# synth.net
KiCad netlist of a schematic drawn in Altium Designer
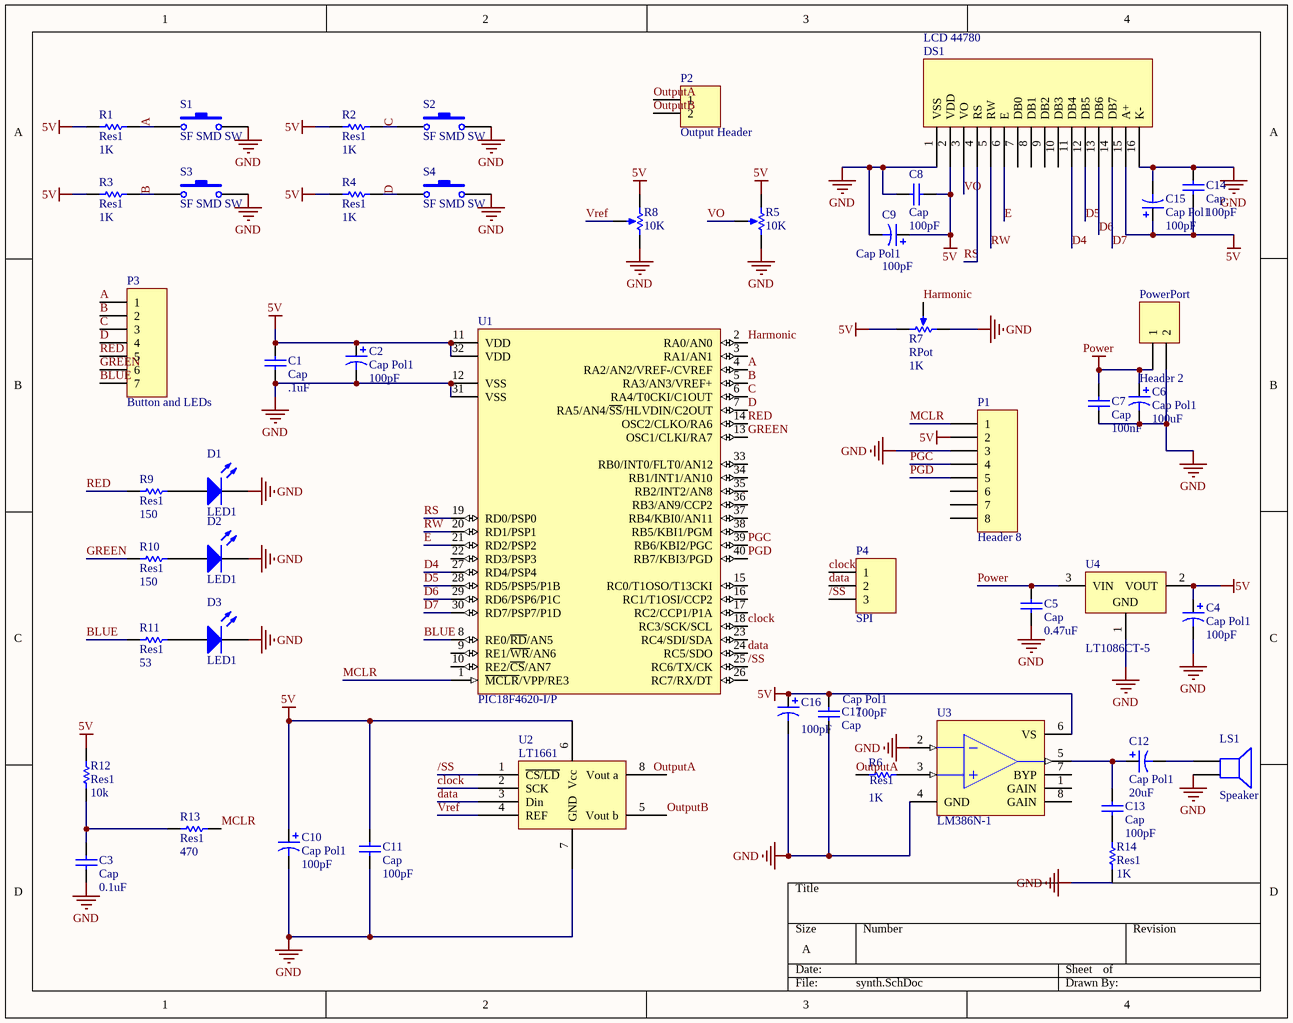
[diagram p0: synth.SchDoc]

(export (version "E")
  (design (tool "Eeschema 10.0.6"))
  (components
    (comp (ref "C1")
      (value "Cap")
      (footprint "RAD-0.3")
      (description "Capacitor")
      (fields (field (name "ALTIUM_VALUE") ".1uF") (field (name "PUBLISHER") "Altium Limited"))
      (libsource (lib "Miscellaneous Devices") (part "Cap"))
    )
    (comp (ref "C2")
      (value "Cap Pol1")
      (footprint "RB7.6-15")
      (description "Polarized Capacitor (Radial)")
      (fields (field (name "ALTIUM_VALUE") "100pF") (field (name "PUBLISHER") "Altium Limited"))
      (libsource (lib "Miscellaneous Devices") (part "Cap Pol1"))
    )
    (comp (ref "C3")
      (value "Cap")
      (footprint "RAD-0.3")
      (description "Capacitor")
      (fields (field (name "ALTIUM_VALUE") "0.1uF") (field (name "PUBLISHER") "Altium Limited"))
      (libsource (lib "Miscellaneous Devices") (part "Cap"))
    )
    (comp (ref "C4")
      (value "Cap Pol1")
      (footprint "RB7.6-15")
      (description "Polarized Capacitor (Radial)")
      (fields (field (name "ALTIUM_VALUE") "100pF") (field (name "PUBLISHER") "Altium Limited"))
      (libsource (lib "Miscellaneous Devices") (part "Cap Pol1"))
    )
    (comp (ref "C5")
      (value "Cap")
      (footprint "RAD-0.3")
      (description "Capacitor")
      (fields (field (name "ALTIUM_VALUE") "0.47uF") (field (name "PUBLISHER") "Altium Limited"))
      (libsource (lib "Miscellaneous Devices") (part "Cap"))
    )
    (comp (ref "C6")
      (value "Cap Pol1")
      (footprint "RB7.6-15")
      (description "Polarized Capacitor (Radial)")
      (fields (field (name "ALTIUM_VALUE") "100uF") (field (name "PUBLISHER") "Altium Limited"))
      (libsource (lib "Miscellaneous Devices") (part "Cap Pol1"))
    )
    (comp (ref "C7")
      (value "Cap")
      (footprint "RAD-0.3")
      (description "Capacitor")
      (fields (field (name "ALTIUM_VALUE") "100nF") (field (name "PUBLISHER") "Altium Limited"))
      (libsource (lib "Miscellaneous Devices") (part "Cap"))
    )
    (comp (ref "C8")
      (value "Cap")
      (footprint "RAD-0.3")
      (description "Capacitor")
      (fields (field (name "ALTIUM_VALUE") "100pF") (field (name "PUBLISHER") "Altium Limited"))
      (libsource (lib "Miscellaneous Devices") (part "Cap"))
    )
    (comp (ref "C9")
      (value "Cap Pol1")
      (footprint "RB7.6-15")
      (description "Polarized Capacitor (Radial)")
      (fields (field (name "ALTIUM_VALUE") "100pF") (field (name "PUBLISHER") "Altium Limited"))
      (libsource (lib "Miscellaneous Devices") (part "Cap Pol1"))
    )
    (comp (ref "C10")
      (value "Cap Pol1")
      (footprint "RB7.6-15")
      (description "Polarized Capacitor (Radial)")
      (fields (field (name "ALTIUM_VALUE") "100pF") (field (name "PUBLISHER") "Altium Limited"))
      (libsource (lib "Miscellaneous Devices") (part "Cap Pol1"))
    )
    (comp (ref "C11")
      (value "Cap")
      (footprint "RAD-0.3")
      (description "Capacitor")
      (fields (field (name "ALTIUM_VALUE") "100pF") (field (name "PUBLISHER") "Altium Limited"))
      (libsource (lib "Miscellaneous Devices") (part "Cap"))
    )
    (comp (ref "C12")
      (value "Cap Pol1")
      (footprint "RB7.6-15")
      (description "Polarized Capacitor (Radial)")
      (fields (field (name "ALTIUM_VALUE") "20uF") (field (name "PUBLISHER") "Altium Limited"))
      (libsource (lib "Miscellaneous Devices") (part "Cap Pol1"))
    )
    (comp (ref "C13")
      (value "Cap")
      (footprint "RAD-0.3")
      (description "Capacitor")
      (fields (field (name "ALTIUM_VALUE") "100pF") (field (name "PUBLISHER") "Altium Limited"))
      (libsource (lib "Miscellaneous Devices") (part "Cap"))
    )
    (comp (ref "C14")
      (value "Cap")
      (footprint "RAD-0.3")
      (description "Capacitor")
      (fields (field (name "ALTIUM_VALUE") "100pF") (field (name "PUBLISHER") "Altium Limited"))
      (libsource (lib "Miscellaneous Devices") (part "Cap"))
    )
    (comp (ref "C15")
      (value "Cap Pol1")
      (footprint "RB7.6-15")
      (description "Polarized Capacitor (Radial)")
      (fields (field (name "ALTIUM_VALUE") "100pF") (field (name "PUBLISHER") "Altium Limited"))
      (libsource (lib "Miscellaneous Devices") (part "Cap Pol1"))
    )
    (comp (ref "C16")
      (value "Cap Pol1")
      (footprint "RB7.6-15")
      (description "Polarized Capacitor (Radial)")
      (fields (field (name "ALTIUM_VALUE") "100pF") (field (name "PUBLISHER") "Altium Limited"))
      (libsource (lib "Miscellaneous Devices") (part "Cap Pol1"))
    )
    (comp (ref "C17")
      (value "Cap")
      (footprint "RAD-0.3")
      (description "Capacitor")
      (fields (field (name "ALTIUM_VALUE") "100pF") (field (name "PUBLISHER") "Altium Limited"))
      (libsource (lib "Miscellaneous Devices") (part "Cap"))
    )
    (comp (ref "D1")
      (value "LED1")
      (footprint "LED-1")
      (description "Typical RED GaAs LED")
      (fields (field (name "PUBLISHER") "Altium Limited"))
      (libsource (lib "Miscellaneous Devices") (part "LED1"))
    )
    (comp (ref "D2")
      (value "LED1")
      (footprint "LED-1")
      (description "Typical RED GaAs LED")
      (fields (field (name "PUBLISHER") "Altium Limited"))
      (libsource (lib "Miscellaneous Devices") (part "LED1"))
    )
    (comp (ref "D3")
      (value "LED1")
      (footprint "LED-1")
      (description "Typical RED GaAs LED")
      (fields (field (name "PUBLISHER") "Altium Limited"))
      (libsource (lib "Miscellaneous Devices") (part "LED1"))
    )
    (comp (ref "DS1")
      (value "LCD 44780")
      (footprint "OLED 16x2")
      (libsource (lib "ECE LIB 21") (part "LCD 44780"))
    )
    (comp (ref "LS1")
      (value "Speaker")
      (footprint "PIN2")
      (description "Loudspeaker")
      (fields (field (name "PUBLISHER") "Altium Limited"))
      (libsource (lib "Miscellaneous Devices") (part "Speaker"))
    )
    (comp (ref "P1")
      (value "Header 8")
      (footprint "HDR1X8")
      (description "Header, 8-Pin")
      (fields (field (name "PUBLISHER") "Altium Limited"))
      (libsource (lib "Miscellaneous Connectors") (part "Header 8"))
    )
    (comp (ref "P2")
      (value "Output Header")
      (footprint "HDR1X2")
      (description "Header, 2-Pin")
      (fields (field (name "PUBLISHER") "Altium Limited"))
      (libsource (lib "Miscellaneous Connectors") (part "Header 2"))
    )
    (comp (ref "P3")
      (value "Button and LEDs")
      (footprint "HDR1X7")
      (description "Header, 7-Pin")
      (fields (field (name "PUBLISHER") "Altium Limited"))
      (libsource (lib "Miscellaneous Connectors") (part "Header 7"))
    )
    (comp (ref "P4")
      (value "SPI")
      (footprint "HDR1X3")
      (description "Header, 3-Pin")
      (fields (field (name "PUBLISHER") "Altium Limited"))
      (libsource (lib "Miscellaneous Connectors") (part "Header 3"))
    )
    (comp (ref "PowerPort")
      (value "Header 2")
      (footprint "HDR1X2")
      (description "Header, 2-Pin")
      (fields (field (name "PUBLISHER") "Altium Limited"))
      (libsource (lib "") (part "Header 2_1"))
    )
    (comp (ref "R1")
      (value "Res1")
      (footprint "AXIAL-0.3")
      (description "Resistor")
      (fields (field (name "ALTIUM_VALUE") "1K") (field (name "PUBLISHER") "Altium Limited"))
      (libsource (lib "Miscellaneous Devices") (part "Res1"))
    )
    (comp (ref "R2")
      (value "Res1")
      (footprint "AXIAL-0.3")
      (description "Resistor")
      (fields (field (name "ALTIUM_VALUE") "1K") (field (name "PUBLISHER") "Altium Limited"))
      (libsource (lib "Miscellaneous Devices") (part "Res1"))
    )
    (comp (ref "R3")
      (value "Res1")
      (footprint "AXIAL-0.3")
      (description "Resistor")
      (fields (field (name "ALTIUM_VALUE") "1K") (field (name "PUBLISHER") "Altium Limited"))
      (libsource (lib "Miscellaneous Devices") (part "Res1"))
    )
    (comp (ref "R4")
      (value "Res1")
      (footprint "AXIAL-0.3")
      (description "Resistor")
      (fields (field (name "ALTIUM_VALUE") "1K") (field (name "PUBLISHER") "Altium Limited"))
      (libsource (lib "Miscellaneous Devices") (part "Res1"))
    )
    (comp (ref "R5")
      (value "10K")
      (footprint "Rpot Square in line")
      (description "Potentiometer")
      (fields (field (name "Comment") "RPot_3") (field (name "PUBLISHER") "Altium Limited"))
      (libsource (lib "ECE LIB 21") (part "RPot_7"))
    )
    (comp (ref "R6")
      (value "Res1")
      (footprint "AXIAL-0.3")
      (description "Resistor")
      (fields (field (name "ALTIUM_VALUE") "1K") (field (name "PUBLISHER") "Altium Limited"))
      (libsource (lib "Miscellaneous Devices") (part "Res1"))
    )
    (comp (ref "R7")
      (value "RPot")
      (footprint "VR5")
      (description "Potentiometer")
      (fields (field (name "ALTIUM_VALUE") "1K") (field (name "PUBLISHER") "Altium Limited"))
      (libsource (lib "Miscellaneous Devices") (part "RPot"))
    )
    (comp (ref "R8")
      (value "10K")
      (footprint "Rpot Square in line")
      (description "Potentiometer")
      (fields (field (name "Comment") "RPot_3") (field (name "PUBLISHER") "Altium Limited"))
      (libsource (lib "ECE LIB 21") (part "RPot_7"))
    )
    (comp (ref "R9")
      (value "Res1")
      (footprint "AXIAL-0.3")
      (description "Resistor")
      (fields (field (name "ALTIUM_VALUE") "150") (field (name "PUBLISHER") "Altium Limited"))
      (libsource (lib "Miscellaneous Devices") (part "Res1"))
    )
    (comp (ref "R10")
      (value "Res1")
      (footprint "AXIAL-0.3")
      (description "Resistor")
      (fields (field (name "ALTIUM_VALUE") "150") (field (name "PUBLISHER") "Altium Limited"))
      (libsource (lib "Miscellaneous Devices") (part "Res1"))
    )
    (comp (ref "R11")
      (value "Res1")
      (footprint "AXIAL-0.3")
      (description "Resistor")
      (fields (field (name "ALTIUM_VALUE") "53") (field (name "PUBLISHER") "Altium Limited"))
      (libsource (lib "Miscellaneous Devices") (part "Res1"))
    )
    (comp (ref "R12")
      (value "Res1")
      (footprint "AXIAL-0.3")
      (description "Resistor")
      (fields (field (name "ALTIUM_VALUE") "10k") (field (name "PUBLISHER") "Altium Limited"))
      (libsource (lib "Miscellaneous Devices") (part "Res1"))
    )
    (comp (ref "R13")
      (value "Res1")
      (footprint "AXIAL-0.3")
      (description "Resistor")
      (fields (field (name "ALTIUM_VALUE") "470") (field (name "PUBLISHER") "Altium Limited"))
      (libsource (lib "Miscellaneous Devices") (part "Res1"))
    )
    (comp (ref "R14")
      (value "Res1")
      (footprint "AXIAL-0.3")
      (description "Resistor")
      (fields (field (name "ALTIUM_VALUE") "1K") (field (name "PUBLISHER") "Altium Limited"))
      (libsource (lib "Miscellaneous Devices") (part "Res1"))
    )
    (comp (ref "S1")
      (value "SF SMD SW")
      (footprint "SW PB")
      (description "DIGIKEY SW400-ND")
      (fields (field (name "PUBLISHER") "Altium Limited"))
      (libsource (lib "ECE LIB 21") (part "SW-PB_1"))
    )
    (comp (ref "S2")
      (value "SF SMD SW")
      (footprint "SW PB")
      (description "DIGIKEY SW400-ND")
      (fields (field (name "PUBLISHER") "Altium Limited"))
      (libsource (lib "ECE LIB 21") (part "SW-PB_1"))
    )
    (comp (ref "S3")
      (value "SF SMD SW")
      (footprint "SW PB")
      (description "DIGIKEY SW400-ND")
      (fields (field (name "PUBLISHER") "Altium Limited"))
      (libsource (lib "ECE LIB 21") (part "SW-PB_1"))
    )
    (comp (ref "S4")
      (value "SF SMD SW")
      (footprint "SW PB")
      (description "DIGIKEY SW400-ND")
      (fields (field (name "PUBLISHER") "Altium Limited"))
      (libsource (lib "ECE LIB 21") (part "SW-PB_1"))
    )
    (comp (ref "U1")
      (value "PIC18F4620-I/P")
      (footprint "PDIP600-P40")
      (libsource (lib "ECE LIB 21") (part "PIC18F4620-I/P"))
    )
    (comp (ref "U2") (value "LT1661") (footprint "DIP-8") (libsource (lib "ECE LIB 21") (part "LT1661")))
    (comp (ref "U3")
      (value "LM386N-1")
      (footprint "DIP-8")
      (description "Low-Voltage Audio Power Amplifier")
      (fields (field (name "PUBLISHER") "Altium Limited"))
      (libsource (lib "ECE LIB 21") (part "LM386N-1"))
    )
    (comp (ref "U4")
      (value "LT1086CT-5")
      (footprint "LT-T-3")
      (description "1.5 A Low Dropout Positive Regulator, 2.55 to 25 V Vin, 5 V Vout, 3-pin FM (T-3), 0 to 150 degC")
      (fields (field (name "MANUFACTURER") "Linear Technology"))
      (libsource (lib "ECE LIB 21") (part "LT1086CT-5"))
    )
  )
  (nets
    (net (code "1") (name "/A") (class "Default")
      (node (ref "P3") (pin "1") (pinfunction "1_1") (pintype "passive"))
      (node (ref "R1") (pin "2") (pinfunction "2_2") (pintype "passive"))
      (node (ref "S1") (pin "1") (pinfunction "1_1") (pintype "passive"))
      (node (ref "U1") (pin "4") (pinfunction "RA2/AN2/VREF-/CVREF_4") (pintype "bidirectional"))
    )
    (net (code "2") (name "/B") (class "Default")
      (node (ref "P3") (pin "2") (pinfunction "2_2") (pintype "passive"))
      (node (ref "R3") (pin "2") (pinfunction "2_2") (pintype "passive"))
      (node (ref "S3") (pin "1") (pinfunction "1_1") (pintype "passive"))
      (node (ref "U1") (pin "5") (pinfunction "RA3/AN3/VREF+_5") (pintype "bidirectional"))
    )
    (net (code "3") (name "/BLUE") (class "Default")
      (node (ref "P3") (pin "7") (pinfunction "7_7") (pintype "passive"))
      (node (ref "R11") (pin "1") (pinfunction "1_1") (pintype "passive"))
      (node (ref "U1") (pin "8") (pinfunction "RE0/~{RD}/AN5_8") (pintype "bidirectional"))
    )
    (net (code "4") (name "/C") (class "Default")
      (node (ref "P3") (pin "3") (pinfunction "3_3") (pintype "passive"))
      (node (ref "R2") (pin "2") (pinfunction "2_2") (pintype "passive"))
      (node (ref "S2") (pin "1") (pinfunction "1_1") (pintype "passive"))
      (node (ref "U1") (pin "6") (pinfunction "RA4/T0CKI/C1OUT_6") (pintype "bidirectional"))
    )
    (net (code "5") (name "/D") (class "Default")
      (node (ref "P3") (pin "4") (pinfunction "4_4") (pintype "passive"))
      (node (ref "R4") (pin "2") (pinfunction "2_2") (pintype "passive"))
      (node (ref "S4") (pin "1") (pinfunction "1_1") (pintype "passive"))
      (node (ref "U1") (pin "7") (pinfunction "RA5/AN4/~{SS}/HLVDIN/C2OUT_7") (pintype "bidirectional"))
    )
    (net (code "6") (name "/D4") (class "Default")
      (node (ref "DS1") (pin "11") (pinfunction "DB4_11") (pintype "passive"))
      (node (ref "U1") (pin "27") (pinfunction "RD4/PSP4_27") (pintype "bidirectional"))
    )
    (net (code "7") (name "/D5") (class "Default")
      (node (ref "DS1") (pin "12") (pinfunction "DB5_12") (pintype "passive"))
      (node (ref "U1") (pin "28") (pinfunction "RD5/PSP5/P1B_28") (pintype "bidirectional"))
    )
    (net (code "8") (name "/D6") (class "Default")
      (node (ref "DS1") (pin "13") (pinfunction "DB6_13") (pintype "passive"))
      (node (ref "U1") (pin "29") (pinfunction "RD6/PSP6/P1C_29") (pintype "bidirectional"))
    )
    (net (code "9") (name "/D7") (class "Default")
      (node (ref "DS1") (pin "14") (pinfunction "DB7_14") (pintype "passive"))
      (node (ref "U1") (pin "30") (pinfunction "RD7/PSP7/P1D_30") (pintype "bidirectional"))
    )
    (net (code "10") (name "/E") (class "Default")
      (node (ref "DS1") (pin "6") (pinfunction "E_6") (pintype "passive"))
      (node (ref "U1") (pin "21") (pinfunction "RD2/PSP2_21") (pintype "bidirectional"))
    )
    (net (code "11") (name "/GREEN") (class "Default")
      (node (ref "P3") (pin "6") (pinfunction "6_6") (pintype "passive"))
      (node (ref "R10") (pin "1") (pinfunction "1_1") (pintype "passive"))
      (node (ref "U1") (pin "13") (pinfunction "OSC1/CLKI/RA7_13") (pintype "bidirectional"))
    )
    (net (code "12") (name "/Harmonic") (class "Default")
      (node (ref "R7") (pin "3") (pinfunction "TAP_3") (pintype "passive"))
      (node (ref "U1") (pin "2") (pinfunction "RA0/AN0_2") (pintype "bidirectional"))
    )
    (net (code "13") (name "/MCLR") (class "Default")
      (node (ref "P1") (pin "1") (pinfunction "1_1") (pintype "passive"))
      (node (ref "R13") (pin "2") (pinfunction "2_2") (pintype "passive"))
      (node (ref "U1") (pin "1") (pinfunction "~{MCLR}/VPP/RE3_1") (pintype "input"))
    )
    (net (code "14") (name "/OutputA") (class "Default")
      (node (ref "P2") (pin "1") (pinfunction "1_1") (pintype "passive"))
      (node (ref "R6") (pin "1") (pinfunction "1_1") (pintype "passive"))
    )
    (net (code "15") (name "/OutputB") (class "Default")
      (node (ref "P2") (pin "2") (pinfunction "2_2") (pintype "passive"))
      (node (ref "U2") (pin "5") (pinfunction "Vout_b_5") (pintype "passive"))
    )
    (net (code "16") (name "/PGC") (class "Default")
      (node (ref "P1") (pin "4") (pinfunction "4_4") (pintype "passive"))
      (node (ref "U1") (pin "39") (pinfunction "RB6/KBI2/PGC_39") (pintype "bidirectional"))
    )
    (net (code "17") (name "/PGD") (class "Default")
      (node (ref "P1") (pin "5") (pinfunction "5_5") (pintype "passive"))
      (node (ref "U1") (pin "40") (pinfunction "RB7/KBI3/PGD_40") (pintype "bidirectional"))
    )
    (net (code "18") (name "/RED") (class "Default")
      (node (ref "P3") (pin "5") (pinfunction "5_5") (pintype "passive"))
      (node (ref "R9") (pin "1") (pinfunction "1_1") (pintype "passive"))
      (node (ref "U1") (pin "14") (pinfunction "OSC2/CLKO/RA6_14") (pintype "bidirectional"))
    )
    (net (code "19") (name "/RS") (class "Default")
      (node (ref "DS1") (pin "4") (pinfunction "RS_4") (pintype "passive"))
      (node (ref "U1") (pin "19") (pinfunction "RD0/PSP0_19") (pintype "bidirectional"))
    )
    (net (code "20") (name "/RW") (class "Default")
      (node (ref "DS1") (pin "5") (pinfunction "RW_5") (pintype "passive"))
      (node (ref "U1") (pin "20") (pinfunction "RD1/PSP1_20") (pintype "bidirectional"))
    )
    (net (code "21") (name "/VO") (class "Default")
      (node (ref "DS1") (pin "3") (pinfunction "VO_3") (pintype "passive"))
      (node (ref "R5") (pin "2") (pinfunction "TAP_2") (pintype "passive"))
    )
    (net (code "22") (name "/Vref") (class "Default")
      (node (ref "R8") (pin "2") (pinfunction "TAP_2") (pintype "passive"))
      (node (ref "U2") (pin "4") (pinfunction "REF_4") (pintype "passive"))
    )
    (net (code "23") (name "/clock") (class "Default")
      (node (ref "P4") (pin "1") (pinfunction "1_1") (pintype "passive"))
      (node (ref "U1") (pin "18") (pinfunction "RC3/SCK/SCL_18") (pintype "bidirectional"))
      (node (ref "U2") (pin "2") (pinfunction "SCK_2") (pintype "passive"))
    )
    (net (code "24") (name "/data") (class "Default")
      (node (ref "P4") (pin "2") (pinfunction "2_2") (pintype "passive"))
      (node (ref "U1") (pin "24") (pinfunction "RC5/SDO_24") (pintype "bidirectional"))
      (node (ref "U2") (pin "3") (pinfunction "Din_3") (pintype "passive"))
    )
    (net (code "25") (name "/{slash}SS") (class "Default")
      (node (ref "P4") (pin "3") (pinfunction "3_3") (pintype "passive"))
      (node (ref "U1") (pin "25") (pinfunction "RC6/TX/CK_25") (pintype "bidirectional"))
      (node (ref "U2") (pin "1") (pinfunction "~{CS/LD}_1") (pintype "passive"))
    )
    (net (code "26") (name "5V") (class "Default")
      (node (ref "C1") (pin "2") (pinfunction "2_2") (pintype "passive"))
      (node (ref "C10") (pin "1") (pinfunction "1_1") (pintype "passive"))
      (node (ref "C11") (pin "2") (pinfunction "2_2") (pintype "passive"))
      (node (ref "C14") (pin "1") (pinfunction "1_1") (pintype "passive"))
      (node (ref "C15") (pin "1") (pinfunction "1_1") (pintype "passive"))
      (node (ref "C16") (pin "1") (pinfunction "1_1") (pintype "passive"))
      (node (ref "C17") (pin "2") (pinfunction "2_2") (pintype "passive"))
      (node (ref "C2") (pin "1") (pinfunction "1_1") (pintype "passive"))
      (node (ref "C4") (pin "1") (pinfunction "1_1") (pintype "passive"))
      (node (ref "C8") (pin "2") (pinfunction "2_2") (pintype "passive"))
      (node (ref "C9") (pin "1") (pinfunction "1_1") (pintype "passive"))
      (node (ref "DS1") (pin "15") (pinfunction "A+_15") (pintype "passive"))
      (node (ref "DS1") (pin "2") (pinfunction "VDD_2") (pintype "passive"))
      (node (ref "P1") (pin "2") (pinfunction "2_2") (pintype "passive"))
      (node (ref "R1") (pin "1") (pinfunction "1_1") (pintype "passive"))
      (node (ref "R12") (pin "2") (pinfunction "2_2") (pintype "passive"))
      (node (ref "R2") (pin "1") (pinfunction "1_1") (pintype "passive"))
      (node (ref "R3") (pin "1") (pinfunction "1_1") (pintype "passive"))
      (node (ref "R4") (pin "1") (pinfunction "1_1") (pintype "passive"))
      (node (ref "R5") (pin "1") (pinfunction "TOP_1") (pintype "passive"))
      (node (ref "R7") (pin "2") (pinfunction "BOT_2") (pintype "passive"))
      (node (ref "R8") (pin "1") (pinfunction "TOP_1") (pintype "passive"))
      (node (ref "U1") (pin "11") (pinfunction "VDD_11") (pintype "power_in"))
      (node (ref "U1") (pin "32") (pinfunction "VDD_32") (pintype "power_in"))
      (node (ref "U2") (pin "6") (pinfunction "Vcc_6") (pintype "passive"))
      (node (ref "U3") (pin "6") (pinfunction "VS_6") (pintype "power_in"))
      (node (ref "U4") (pin "2") (pinfunction "VOUT_2") (pintype "power_in"))
    )
    (net (code "27") (name "GND") (class "Default")
      (node (ref "C1") (pin "1") (pinfunction "1_1") (pintype "passive"))
      (node (ref "C10") (pin "2") (pinfunction "2_2") (pintype "passive"))
      (node (ref "C11") (pin "1") (pinfunction "1_1") (pintype "passive"))
      (node (ref "C14") (pin "2") (pinfunction "2_2") (pintype "passive"))
      (node (ref "C15") (pin "2") (pinfunction "2_2") (pintype "passive"))
      (node (ref "C16") (pin "2") (pinfunction "2_2") (pintype "passive"))
      (node (ref "C17") (pin "1") (pinfunction "1_1") (pintype "passive"))
      (node (ref "C2") (pin "2") (pinfunction "2_2") (pintype "passive"))
      (node (ref "C3") (pin "1") (pinfunction "1_1") (pintype "passive"))
      (node (ref "C4") (pin "2") (pinfunction "2_2") (pintype "passive"))
      (node (ref "C5") (pin "1") (pinfunction "1_1") (pintype "passive"))
      (node (ref "C6") (pin "2") (pinfunction "2_2") (pintype "passive"))
      (node (ref "C7") (pin "1") (pinfunction "1_1") (pintype "passive"))
      (node (ref "C8") (pin "1") (pinfunction "1_1") (pintype "passive"))
      (node (ref "C9") (pin "2") (pinfunction "2_2") (pintype "passive"))
      (node (ref "D1") (pin "2") (pinfunction "K_2") (pintype "passive"))
      (node (ref "D2") (pin "2") (pinfunction "K_2") (pintype "passive"))
      (node (ref "D3") (pin "2") (pinfunction "K_2") (pintype "passive"))
      (node (ref "DS1") (pin "1") (pinfunction "VSS_1") (pintype "passive"))
      (node (ref "DS1") (pin "16") (pinfunction "K-_16") (pintype "passive"))
      (node (ref "LS1") (pin "2") (pinfunction "2_2") (pintype "passive"))
      (node (ref "P1") (pin "3") (pinfunction "3_3") (pintype "passive"))
      (node (ref "PowerPort") (pin "2") (pinfunction "2_2") (pintype "passive"))
      (node (ref "R14") (pin "1") (pinfunction "1_1") (pintype "passive"))
      (node (ref "R5") (pin "3") (pinfunction "BOT_3") (pintype "passive"))
      (node (ref "R7") (pin "1") (pinfunction "TOP_1") (pintype "passive"))
      (node (ref "R8") (pin "3") (pinfunction "BOT_3") (pintype "passive"))
      (node (ref "S1") (pin "2") (pinfunction "2_2") (pintype "passive"))
      (node (ref "S2") (pin "2") (pinfunction "2_2") (pintype "passive"))
      (node (ref "S3") (pin "2") (pinfunction "2_2") (pintype "passive"))
      (node (ref "S4") (pin "2") (pinfunction "2_2") (pintype "passive"))
      (node (ref "U1") (pin "12") (pinfunction "VSS_12") (pintype "power_in"))
      (node (ref "U1") (pin "31") (pinfunction "VSS_31") (pintype "power_in"))
      (node (ref "U2") (pin "7") (pinfunction "GND_7") (pintype "passive"))
      (node (ref "U3") (pin "2") (pinfunction "IN-_2") (pintype "input"))
      (node (ref "U3") (pin "4") (pinfunction "GND_4") (pintype "power_in"))
      (node (ref "U4") (pin "1") (pinfunction "GND_1") (pintype "power_in"))
    )
    (net (code "28") (name "Net-(C3-Pad2)") (class "Default")
      (node (ref "C3") (pin "2") (pinfunction "2_2") (pintype "passive"))
      (node (ref "R12") (pin "1") (pinfunction "1_1") (pintype "passive"))
      (node (ref "R13") (pin "1") (pinfunction "1_1") (pintype "passive"))
    )
    (net (code "29") (name "Net-(C12-Pad2)") (class "Default")
      (node (ref "C12") (pin "2") (pinfunction "2_2") (pintype "passive"))
      (node (ref "LS1") (pin "1") (pinfunction "1_1") (pintype "passive"))
    )
    (net (code "30") (name "Net-(C13-Pad1)") (class "Default")
      (node (ref "C13") (pin "1") (pinfunction "1_1") (pintype "passive"))
      (node (ref "R14") (pin "2") (pinfunction "2_2") (pintype "passive"))
    )
    (net (code "31") (name "Net-(D1-A)") (class "Default")
      (node (ref "D1") (pin "1") (pinfunction "A_1") (pintype "passive"))
      (node (ref "R9") (pin "2") (pinfunction "2_2") (pintype "passive"))
    )
    (net (code "32") (name "Net-(D2-A)") (class "Default")
      (node (ref "D2") (pin "1") (pinfunction "A_1") (pintype "passive"))
      (node (ref "R10") (pin "2") (pinfunction "2_2") (pintype "passive"))
    )
    (net (code "33") (name "Net-(D3-A)") (class "Default")
      (node (ref "D3") (pin "1") (pinfunction "A_1") (pintype "passive"))
      (node (ref "R11") (pin "2") (pinfunction "2_2") (pintype "passive"))
    )
    (net (code "34") (name "Net-(U3-IN+)") (class "Default")
      (node (ref "R6") (pin "2") (pinfunction "2_2") (pintype "passive"))
      (node (ref "U3") (pin "3") (pinfunction "IN+_3") (pintype "input"))
    )
    (net (code "35") (name "Net-(U3-OUT)") (class "Default")
      (node (ref "C12") (pin "1") (pinfunction "1_1") (pintype "passive"))
      (node (ref "C13") (pin "2") (pinfunction "2_2") (pintype "passive"))
      (node (ref "U3") (pin "5") (pinfunction "OUT_5") (pintype "output"))
    )
    (net (code "36") (name "Power") (class "Default")
      (node (ref "C5") (pin "2") (pinfunction "2_2") (pintype "passive"))
      (node (ref "C6") (pin "1") (pinfunction "1_1") (pintype "passive"))
      (node (ref "C7") (pin "2") (pinfunction "2_2") (pintype "passive"))
      (node (ref "PowerPort") (pin "1") (pinfunction "1_1") (pintype "passive"))
      (node (ref "U4") (pin "3") (pinfunction "VIN_3") (pintype "power_in"))
    )
    (net (code "37") (name "unconnected-(DS1-DB0-Pad7)") (class "Default")
      (node (ref "DS1") (pin "7") (pinfunction "DB0_7") (pintype "passive"))
    )
    (net (code "38") (name "unconnected-(DS1-DB1-Pad8)") (class "Default")
      (node (ref "DS1") (pin "8") (pinfunction "DB1_8") (pintype "passive"))
    )
    (net (code "39") (name "unconnected-(DS1-DB2-Pad9)") (class "Default")
      (node (ref "DS1") (pin "9") (pinfunction "DB2_9") (pintype "passive"))
    )
    (net (code "40") (name "unconnected-(DS1-DB3-Pad10)") (class "Default")
      (node (ref "DS1") (pin "10") (pinfunction "DB3_10") (pintype "passive"))
    )
    (net (code "41") (name "unconnected-(P1-Pad6)") (class "Default")
      (node (ref "P1") (pin "6") (pinfunction "6_6") (pintype "passive"))
    )
    (net (code "42") (name "unconnected-(P1-Pad7)") (class "Default")
      (node (ref "P1") (pin "7") (pinfunction "7_7") (pintype "passive"))
    )
    (net (code "43") (name "unconnected-(P1-Pad8)") (class "Default")
      (node (ref "P1") (pin "8") (pinfunction "8_8") (pintype "passive"))
    )
    (net (code "44") (name "unconnected-(U1-RA1{slash}AN1-Pad3)") (class "Default")
      (node (ref "U1") (pin "3") (pinfunction "RA1/AN1_3") (pintype "bidirectional"))
    )
    (net (code "45") (name "unconnected-(U1-RB0{slash}INT0{slash}FLT0{slash}AN12-Pad33)") (class "Default")
      (node (ref "U1") (pin "33") (pinfunction "RB0/INT0/FLT0/AN12_33") (pintype "bidirectional"))
    )
    (net (code "46") (name "unconnected-(U1-RB1{slash}INT1{slash}AN10-Pad34)") (class "Default")
      (node (ref "U1") (pin "34") (pinfunction "RB1/INT1/AN10_34") (pintype "bidirectional"))
    )
    (net (code "47") (name "unconnected-(U1-RB2{slash}INT2{slash}AN8-Pad35)") (class "Default")
      (node (ref "U1") (pin "35") (pinfunction "RB2/INT2/AN8_35") (pintype "bidirectional"))
    )
    (net (code "48") (name "unconnected-(U1-RB3{slash}AN9{slash}CCP2-Pad36)") (class "Default")
      (node (ref "U1") (pin "36") (pinfunction "RB3/AN9/CCP2_36") (pintype "bidirectional"))
    )
    (net (code "49") (name "unconnected-(U1-RB4{slash}KBI0{slash}AN11-Pad37)") (class "Default")
      (node (ref "U1") (pin "37") (pinfunction "RB4/KBI0/AN11_37") (pintype "bidirectional"))
    )
    (net (code "50") (name "unconnected-(U1-RB5{slash}KBI1{slash}PGM-Pad38)") (class "Default")
      (node (ref "U1") (pin "38") (pinfunction "RB5/KBI1/PGM_38") (pintype "bidirectional"))
    )
    (net (code "51") (name "unconnected-(U1-RC0{slash}T1OSO{slash}T13CKI-Pad15)") (class "Default")
      (node (ref "U1") (pin "15") (pinfunction "RC0/T1OSO/T13CKI_15") (pintype "bidirectional"))
    )
    (net (code "52") (name "unconnected-(U1-RC1{slash}T1OSI{slash}CCP2-Pad16)") (class "Default")
      (node (ref "U1") (pin "16") (pinfunction "RC1/T1OSI/CCP2_16") (pintype "bidirectional"))
    )
    (net (code "53") (name "unconnected-(U1-RC2{slash}CCP1{slash}P1A-Pad17)") (class "Default")
      (node (ref "U1") (pin "17") (pinfunction "RC2/CCP1/P1A_17") (pintype "bidirectional"))
    )
    (net (code "54") (name "unconnected-(U1-RC4{slash}SDI{slash}SDA-Pad23)") (class "Default")
      (node (ref "U1") (pin "23") (pinfunction "RC4/SDI/SDA_23") (pintype "bidirectional"))
    )
    (net (code "55") (name "unconnected-(U1-RC7{slash}RX{slash}DT-Pad26)") (class "Default")
      (node (ref "U1") (pin "26") (pinfunction "RC7/RX/DT_26") (pintype "bidirectional"))
    )
    (net (code "56") (name "unconnected-(U1-RD3{slash}PSP3-Pad22)") (class "Default")
      (node (ref "U1") (pin "22") (pinfunction "RD3/PSP3_22") (pintype "bidirectional"))
    )
    (net (code "57") (name "unconnected-(U1-RE1{slash}~{WR}{slash}AN6-Pad9)") (class "Default")
      (node (ref "U1") (pin "9") (pinfunction "RE1/~{WR}/AN6_9") (pintype "bidirectional"))
    )
    (net (code "58") (name "unconnected-(U1-RE2{slash}~{CS}{slash}AN7-Pad10)") (class "Default")
      (node (ref "U1") (pin "10") (pinfunction "RE2/~{CS}/AN7_10") (pintype "bidirectional"))
    )
    (net (code "59") (name "unconnected-(U2-Vout_a-Pad8)") (class "Default")
      (node (ref "U2") (pin "8") (pinfunction "Vout_a_8") (pintype "passive"))
    )
    (net (code "60") (name "unconnected-(U3-BYP-Pad7)") (class "Default")
      (node (ref "U3") (pin "7") (pinfunction "BYP_7") (pintype "passive"))
    )
    (net (code "61") (name "unconnected-(U3-GAIN-Pad1)") (class "Default")
      (node (ref "U3") (pin "1") (pinfunction "GAIN_1") (pintype "passive"))
    )
    (net (code "62") (name "unconnected-(U3-GAIN-Pad8)") (class "Default")
      (node (ref "U3") (pin "8") (pinfunction "GAIN_8") (pintype "passive"))
    )
  )
)
